# PC104Breakout.net
KiCad netlist of a schematic drawn in Altium Designer
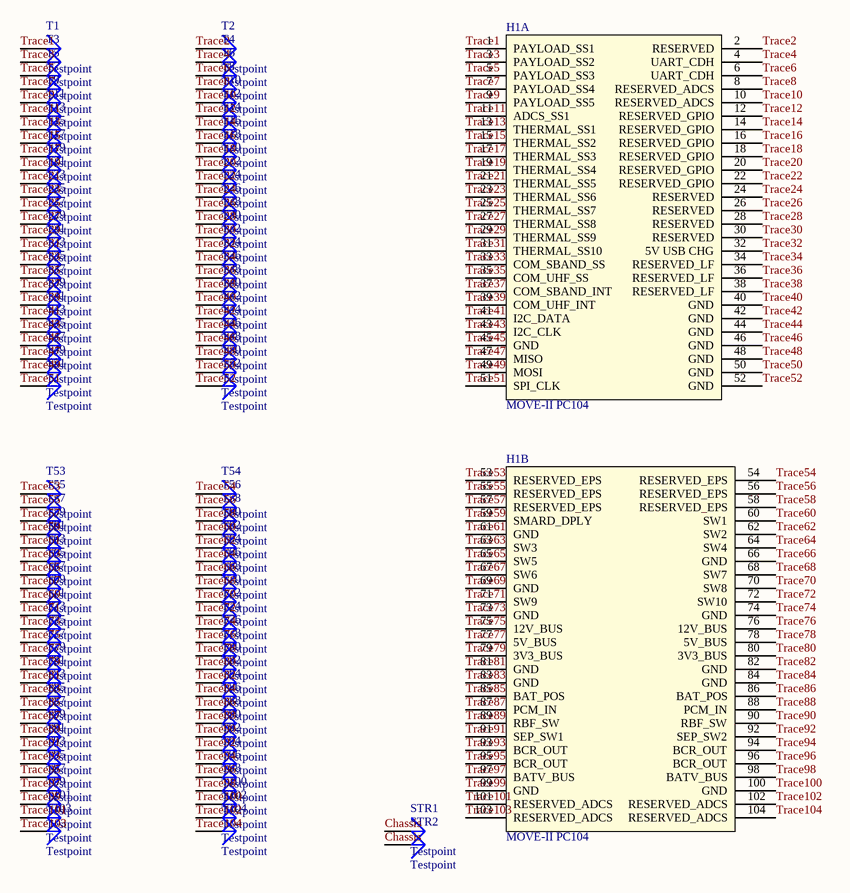
[diagram p0: PC104Breakout.SchDoc]

(export (version "E")
  (design (tool "Eeschema 10.0.6"))
  (components
    (comp (ref "H1")
      (value "MOVE-II PC104")
      (footprint "PC104")
      (libsource (lib "PC104_singleHeader") (part "MOVE-II PC104"))
    )
    (comp (ref "STR1")
      (value "Testpoint")
      (footprint "PIN1")
      (description "Plug")
      (fields (field (name "PUBLISHER") "Altium Limited"))
      (libsource (lib "Miscellaneous Connectors") (part "Plug"))
    )
    (comp (ref "STR2")
      (value "Testpoint")
      (footprint "PIN1")
      (description "Plug")
      (fields (field (name "PUBLISHER") "Altium Limited"))
      (libsource (lib "Miscellaneous Connectors") (part "Plug"))
    )
    (comp (ref "T1")
      (value "Testpoint")
      (footprint "PIN1")
      (description "Plug")
      (fields (field (name "PUBLISHER") "Altium Limited"))
      (libsource (lib "Miscellaneous Connectors") (part "Plug"))
    )
    (comp (ref "T2")
      (value "Testpoint")
      (footprint "PIN1")
      (description "Plug")
      (fields (field (name "PUBLISHER") "Altium Limited"))
      (libsource (lib "Miscellaneous Connectors") (part "Plug"))
    )
    (comp (ref "T3")
      (value "Testpoint")
      (footprint "PIN1")
      (description "Plug")
      (fields (field (name "PUBLISHER") "Altium Limited"))
      (libsource (lib "Miscellaneous Connectors") (part "Plug"))
    )
    (comp (ref "T4")
      (value "Testpoint")
      (footprint "PIN1")
      (description "Plug")
      (fields (field (name "PUBLISHER") "Altium Limited"))
      (libsource (lib "Miscellaneous Connectors") (part "Plug"))
    )
    (comp (ref "T5")
      (value "Testpoint")
      (footprint "PIN1")
      (description "Plug")
      (fields (field (name "PUBLISHER") "Altium Limited"))
      (libsource (lib "Miscellaneous Connectors") (part "Plug"))
    )
    (comp (ref "T6")
      (value "Testpoint")
      (footprint "PIN1")
      (description "Plug")
      (fields (field (name "PUBLISHER") "Altium Limited"))
      (libsource (lib "Miscellaneous Connectors") (part "Plug"))
    )
    (comp (ref "T7")
      (value "Testpoint")
      (footprint "PIN1")
      (description "Plug")
      (fields (field (name "PUBLISHER") "Altium Limited"))
      (libsource (lib "Miscellaneous Connectors") (part "Plug"))
    )
    (comp (ref "T8")
      (value "Testpoint")
      (footprint "PIN1")
      (description "Plug")
      (fields (field (name "PUBLISHER") "Altium Limited"))
      (libsource (lib "Miscellaneous Connectors") (part "Plug"))
    )
    (comp (ref "T9")
      (value "Testpoint")
      (footprint "PIN1")
      (description "Plug")
      (fields (field (name "PUBLISHER") "Altium Limited"))
      (libsource (lib "Miscellaneous Connectors") (part "Plug"))
    )
    (comp (ref "T10")
      (value "Testpoint")
      (footprint "PIN1")
      (description "Plug")
      (fields (field (name "PUBLISHER") "Altium Limited"))
      (libsource (lib "Miscellaneous Connectors") (part "Plug"))
    )
    (comp (ref "T11")
      (value "Testpoint")
      (footprint "PIN1")
      (description "Plug")
      (fields (field (name "PUBLISHER") "Altium Limited"))
      (libsource (lib "Miscellaneous Connectors") (part "Plug"))
    )
    (comp (ref "T12")
      (value "Testpoint")
      (footprint "PIN1")
      (description "Plug")
      (fields (field (name "PUBLISHER") "Altium Limited"))
      (libsource (lib "Miscellaneous Connectors") (part "Plug"))
    )
    (comp (ref "T13")
      (value "Testpoint")
      (footprint "PIN1")
      (description "Plug")
      (fields (field (name "PUBLISHER") "Altium Limited"))
      (libsource (lib "Miscellaneous Connectors") (part "Plug"))
    )
    (comp (ref "T14")
      (value "Testpoint")
      (footprint "PIN1")
      (description "Plug")
      (fields (field (name "PUBLISHER") "Altium Limited"))
      (libsource (lib "Miscellaneous Connectors") (part "Plug"))
    )
    (comp (ref "T15")
      (value "Testpoint")
      (footprint "PIN1")
      (description "Plug")
      (fields (field (name "PUBLISHER") "Altium Limited"))
      (libsource (lib "Miscellaneous Connectors") (part "Plug"))
    )
    (comp (ref "T16")
      (value "Testpoint")
      (footprint "PIN1")
      (description "Plug")
      (fields (field (name "PUBLISHER") "Altium Limited"))
      (libsource (lib "Miscellaneous Connectors") (part "Plug"))
    )
    (comp (ref "T17")
      (value "Testpoint")
      (footprint "PIN1")
      (description "Plug")
      (fields (field (name "PUBLISHER") "Altium Limited"))
      (libsource (lib "Miscellaneous Connectors") (part "Plug"))
    )
    (comp (ref "T18")
      (value "Testpoint")
      (footprint "PIN1")
      (description "Plug")
      (fields (field (name "PUBLISHER") "Altium Limited"))
      (libsource (lib "Miscellaneous Connectors") (part "Plug"))
    )
    (comp (ref "T19")
      (value "Testpoint")
      (footprint "PIN1")
      (description "Plug")
      (fields (field (name "PUBLISHER") "Altium Limited"))
      (libsource (lib "Miscellaneous Connectors") (part "Plug"))
    )
    (comp (ref "T20")
      (value "Testpoint")
      (footprint "PIN1")
      (description "Plug")
      (fields (field (name "PUBLISHER") "Altium Limited"))
      (libsource (lib "Miscellaneous Connectors") (part "Plug"))
    )
    (comp (ref "T21")
      (value "Testpoint")
      (footprint "PIN1")
      (description "Plug")
      (fields (field (name "PUBLISHER") "Altium Limited"))
      (libsource (lib "Miscellaneous Connectors") (part "Plug"))
    )
    (comp (ref "T22")
      (value "Testpoint")
      (footprint "PIN1")
      (description "Plug")
      (fields (field (name "PUBLISHER") "Altium Limited"))
      (libsource (lib "Miscellaneous Connectors") (part "Plug"))
    )
    (comp (ref "T23")
      (value "Testpoint")
      (footprint "PIN1")
      (description "Plug")
      (fields (field (name "PUBLISHER") "Altium Limited"))
      (libsource (lib "Miscellaneous Connectors") (part "Plug"))
    )
    (comp (ref "T24")
      (value "Testpoint")
      (footprint "PIN1")
      (description "Plug")
      (fields (field (name "PUBLISHER") "Altium Limited"))
      (libsource (lib "Miscellaneous Connectors") (part "Plug"))
    )
    (comp (ref "T25")
      (value "Testpoint")
      (footprint "PIN1")
      (description "Plug")
      (fields (field (name "PUBLISHER") "Altium Limited"))
      (libsource (lib "Miscellaneous Connectors") (part "Plug"))
    )
    (comp (ref "T26")
      (value "Testpoint")
      (footprint "PIN1")
      (description "Plug")
      (fields (field (name "PUBLISHER") "Altium Limited"))
      (libsource (lib "Miscellaneous Connectors") (part "Plug"))
    )
    (comp (ref "T27")
      (value "Testpoint")
      (footprint "PIN1")
      (description "Plug")
      (fields (field (name "PUBLISHER") "Altium Limited"))
      (libsource (lib "Miscellaneous Connectors") (part "Plug"))
    )
    (comp (ref "T28")
      (value "Testpoint")
      (footprint "PIN1")
      (description "Plug")
      (fields (field (name "PUBLISHER") "Altium Limited"))
      (libsource (lib "Miscellaneous Connectors") (part "Plug"))
    )
    (comp (ref "T29")
      (value "Testpoint")
      (footprint "PIN1")
      (description "Plug")
      (fields (field (name "PUBLISHER") "Altium Limited"))
      (libsource (lib "Miscellaneous Connectors") (part "Plug"))
    )
    (comp (ref "T30")
      (value "Testpoint")
      (footprint "PIN1")
      (description "Plug")
      (fields (field (name "PUBLISHER") "Altium Limited"))
      (libsource (lib "Miscellaneous Connectors") (part "Plug"))
    )
    (comp (ref "T31")
      (value "Testpoint")
      (footprint "PIN1")
      (description "Plug")
      (fields (field (name "PUBLISHER") "Altium Limited"))
      (libsource (lib "Miscellaneous Connectors") (part "Plug"))
    )
    (comp (ref "T32")
      (value "Testpoint")
      (footprint "PIN1")
      (description "Plug")
      (fields (field (name "PUBLISHER") "Altium Limited"))
      (libsource (lib "Miscellaneous Connectors") (part "Plug"))
    )
    (comp (ref "T33")
      (value "Testpoint")
      (footprint "PIN1")
      (description "Plug")
      (fields (field (name "PUBLISHER") "Altium Limited"))
      (libsource (lib "Miscellaneous Connectors") (part "Plug"))
    )
    (comp (ref "T34")
      (value "Testpoint")
      (footprint "PIN1")
      (description "Plug")
      (fields (field (name "PUBLISHER") "Altium Limited"))
      (libsource (lib "Miscellaneous Connectors") (part "Plug"))
    )
    (comp (ref "T35")
      (value "Testpoint")
      (footprint "PIN1")
      (description "Plug")
      (fields (field (name "PUBLISHER") "Altium Limited"))
      (libsource (lib "Miscellaneous Connectors") (part "Plug"))
    )
    (comp (ref "T36")
      (value "Testpoint")
      (footprint "PIN1")
      (description "Plug")
      (fields (field (name "PUBLISHER") "Altium Limited"))
      (libsource (lib "Miscellaneous Connectors") (part "Plug"))
    )
    (comp (ref "T37")
      (value "Testpoint")
      (footprint "PIN1")
      (description "Plug")
      (fields (field (name "PUBLISHER") "Altium Limited"))
      (libsource (lib "Miscellaneous Connectors") (part "Plug"))
    )
    (comp (ref "T38")
      (value "Testpoint")
      (footprint "PIN1")
      (description "Plug")
      (fields (field (name "PUBLISHER") "Altium Limited"))
      (libsource (lib "Miscellaneous Connectors") (part "Plug"))
    )
    (comp (ref "T39")
      (value "Testpoint")
      (footprint "PIN1")
      (description "Plug")
      (fields (field (name "PUBLISHER") "Altium Limited"))
      (libsource (lib "Miscellaneous Connectors") (part "Plug"))
    )
    (comp (ref "T40")
      (value "Testpoint")
      (footprint "PIN1")
      (description "Plug")
      (fields (field (name "PUBLISHER") "Altium Limited"))
      (libsource (lib "Miscellaneous Connectors") (part "Plug"))
    )
    (comp (ref "T41")
      (value "Testpoint")
      (footprint "PIN1")
      (description "Plug")
      (fields (field (name "PUBLISHER") "Altium Limited"))
      (libsource (lib "Miscellaneous Connectors") (part "Plug"))
    )
    (comp (ref "T42")
      (value "Testpoint")
      (footprint "PIN1")
      (description "Plug")
      (fields (field (name "PUBLISHER") "Altium Limited"))
      (libsource (lib "Miscellaneous Connectors") (part "Plug"))
    )
    (comp (ref "T43")
      (value "Testpoint")
      (footprint "PIN1")
      (description "Plug")
      (fields (field (name "PUBLISHER") "Altium Limited"))
      (libsource (lib "Miscellaneous Connectors") (part "Plug"))
    )
    (comp (ref "T44")
      (value "Testpoint")
      (footprint "PIN1")
      (description "Plug")
      (fields (field (name "PUBLISHER") "Altium Limited"))
      (libsource (lib "Miscellaneous Connectors") (part "Plug"))
    )
    (comp (ref "T45")
      (value "Testpoint")
      (footprint "PIN1")
      (description "Plug")
      (fields (field (name "PUBLISHER") "Altium Limited"))
      (libsource (lib "Miscellaneous Connectors") (part "Plug"))
    )
    (comp (ref "T46")
      (value "Testpoint")
      (footprint "PIN1")
      (description "Plug")
      (fields (field (name "PUBLISHER") "Altium Limited"))
      (libsource (lib "Miscellaneous Connectors") (part "Plug"))
    )
    (comp (ref "T47")
      (value "Testpoint")
      (footprint "PIN1")
      (description "Plug")
      (fields (field (name "PUBLISHER") "Altium Limited"))
      (libsource (lib "Miscellaneous Connectors") (part "Plug"))
    )
    (comp (ref "T48")
      (value "Testpoint")
      (footprint "PIN1")
      (description "Plug")
      (fields (field (name "PUBLISHER") "Altium Limited"))
      (libsource (lib "Miscellaneous Connectors") (part "Plug"))
    )
    (comp (ref "T49")
      (value "Testpoint")
      (footprint "PIN1")
      (description "Plug")
      (fields (field (name "PUBLISHER") "Altium Limited"))
      (libsource (lib "Miscellaneous Connectors") (part "Plug"))
    )
    (comp (ref "T50")
      (value "Testpoint")
      (footprint "PIN1")
      (description "Plug")
      (fields (field (name "PUBLISHER") "Altium Limited"))
      (libsource (lib "Miscellaneous Connectors") (part "Plug"))
    )
    (comp (ref "T51")
      (value "Testpoint")
      (footprint "PIN1")
      (description "Plug")
      (fields (field (name "PUBLISHER") "Altium Limited"))
      (libsource (lib "Miscellaneous Connectors") (part "Plug"))
    )
    (comp (ref "T52")
      (value "Testpoint")
      (footprint "PIN1")
      (description "Plug")
      (fields (field (name "PUBLISHER") "Altium Limited"))
      (libsource (lib "Miscellaneous Connectors") (part "Plug"))
    )
    (comp (ref "T53")
      (value "Testpoint")
      (footprint "PIN1")
      (description "Plug")
      (fields (field (name "PUBLISHER") "Altium Limited"))
      (libsource (lib "Miscellaneous Connectors") (part "Plug"))
    )
    (comp (ref "T54")
      (value "Testpoint")
      (footprint "PIN1")
      (description "Plug")
      (fields (field (name "PUBLISHER") "Altium Limited"))
      (libsource (lib "Miscellaneous Connectors") (part "Plug"))
    )
    (comp (ref "T55")
      (value "Testpoint")
      (footprint "PIN1")
      (description "Plug")
      (fields (field (name "PUBLISHER") "Altium Limited"))
      (libsource (lib "Miscellaneous Connectors") (part "Plug"))
    )
    (comp (ref "T56")
      (value "Testpoint")
      (footprint "PIN1")
      (description "Plug")
      (fields (field (name "PUBLISHER") "Altium Limited"))
      (libsource (lib "Miscellaneous Connectors") (part "Plug"))
    )
    (comp (ref "T57")
      (value "Testpoint")
      (footprint "PIN1")
      (description "Plug")
      (fields (field (name "PUBLISHER") "Altium Limited"))
      (libsource (lib "Miscellaneous Connectors") (part "Plug"))
    )
    (comp (ref "T58")
      (value "Testpoint")
      (footprint "PIN1")
      (description "Plug")
      (fields (field (name "PUBLISHER") "Altium Limited"))
      (libsource (lib "Miscellaneous Connectors") (part "Plug"))
    )
    (comp (ref "T59")
      (value "Testpoint")
      (footprint "PIN1")
      (description "Plug")
      (fields (field (name "PUBLISHER") "Altium Limited"))
      (libsource (lib "Miscellaneous Connectors") (part "Plug"))
    )
    (comp (ref "T60")
      (value "Testpoint")
      (footprint "PIN1")
      (description "Plug")
      (fields (field (name "PUBLISHER") "Altium Limited"))
      (libsource (lib "Miscellaneous Connectors") (part "Plug"))
    )
    (comp (ref "T61")
      (value "Testpoint")
      (footprint "PIN1")
      (description "Plug")
      (fields (field (name "PUBLISHER") "Altium Limited"))
      (libsource (lib "Miscellaneous Connectors") (part "Plug"))
    )
    (comp (ref "T62")
      (value "Testpoint")
      (footprint "PIN1")
      (description "Plug")
      (fields (field (name "PUBLISHER") "Altium Limited"))
      (libsource (lib "Miscellaneous Connectors") (part "Plug"))
    )
    (comp (ref "T63")
      (value "Testpoint")
      (footprint "PIN1")
      (description "Plug")
      (fields (field (name "PUBLISHER") "Altium Limited"))
      (libsource (lib "Miscellaneous Connectors") (part "Plug"))
    )
    (comp (ref "T64")
      (value "Testpoint")
      (footprint "PIN1")
      (description "Plug")
      (fields (field (name "PUBLISHER") "Altium Limited"))
      (libsource (lib "Miscellaneous Connectors") (part "Plug"))
    )
    (comp (ref "T65")
      (value "Testpoint")
      (footprint "PIN1")
      (description "Plug")
      (fields (field (name "PUBLISHER") "Altium Limited"))
      (libsource (lib "Miscellaneous Connectors") (part "Plug"))
    )
    (comp (ref "T66")
      (value "Testpoint")
      (footprint "PIN1")
      (description "Plug")
      (fields (field (name "PUBLISHER") "Altium Limited"))
      (libsource (lib "Miscellaneous Connectors") (part "Plug"))
    )
    (comp (ref "T67")
      (value "Testpoint")
      (footprint "PIN1")
      (description "Plug")
      (fields (field (name "PUBLISHER") "Altium Limited"))
      (libsource (lib "Miscellaneous Connectors") (part "Plug"))
    )
    (comp (ref "T68")
      (value "Testpoint")
      (footprint "PIN1")
      (description "Plug")
      (fields (field (name "PUBLISHER") "Altium Limited"))
      (libsource (lib "Miscellaneous Connectors") (part "Plug"))
    )
    (comp (ref "T69")
      (value "Testpoint")
      (footprint "PIN1")
      (description "Plug")
      (fields (field (name "PUBLISHER") "Altium Limited"))
      (libsource (lib "Miscellaneous Connectors") (part "Plug"))
    )
    (comp (ref "T70")
      (value "Testpoint")
      (footprint "PIN1")
      (description "Plug")
      (fields (field (name "PUBLISHER") "Altium Limited"))
      (libsource (lib "Miscellaneous Connectors") (part "Plug"))
    )
    (comp (ref "T71")
      (value "Testpoint")
      (footprint "PIN1")
      (description "Plug")
      (fields (field (name "PUBLISHER") "Altium Limited"))
      (libsource (lib "Miscellaneous Connectors") (part "Plug"))
    )
    (comp (ref "T72")
      (value "Testpoint")
      (footprint "PIN1")
      (description "Plug")
      (fields (field (name "PUBLISHER") "Altium Limited"))
      (libsource (lib "Miscellaneous Connectors") (part "Plug"))
    )
    (comp (ref "T73")
      (value "Testpoint")
      (footprint "PIN1")
      (description "Plug")
      (fields (field (name "PUBLISHER") "Altium Limited"))
      (libsource (lib "Miscellaneous Connectors") (part "Plug"))
    )
    (comp (ref "T74")
      (value "Testpoint")
      (footprint "PIN1")
      (description "Plug")
      (fields (field (name "PUBLISHER") "Altium Limited"))
      (libsource (lib "Miscellaneous Connectors") (part "Plug"))
    )
    (comp (ref "T75")
      (value "Testpoint")
      (footprint "PIN1")
      (description "Plug")
      (fields (field (name "PUBLISHER") "Altium Limited"))
      (libsource (lib "Miscellaneous Connectors") (part "Plug"))
    )
    (comp (ref "T76")
      (value "Testpoint")
      (footprint "PIN1")
      (description "Plug")
      (fields (field (name "PUBLISHER") "Altium Limited"))
      (libsource (lib "Miscellaneous Connectors") (part "Plug"))
    )
    (comp (ref "T77")
      (value "Testpoint")
      (footprint "PIN1")
      (description "Plug")
      (fields (field (name "PUBLISHER") "Altium Limited"))
      (libsource (lib "Miscellaneous Connectors") (part "Plug"))
    )
    (comp (ref "T78")
      (value "Testpoint")
      (footprint "PIN1")
      (description "Plug")
      (fields (field (name "PUBLISHER") "Altium Limited"))
      (libsource (lib "Miscellaneous Connectors") (part "Plug"))
    )
    (comp (ref "T79")
      (value "Testpoint")
      (footprint "PIN1")
      (description "Plug")
      (fields (field (name "PUBLISHER") "Altium Limited"))
      (libsource (lib "Miscellaneous Connectors") (part "Plug"))
    )
    (comp (ref "T80")
      (value "Testpoint")
      (footprint "PIN1")
      (description "Plug")
      (fields (field (name "PUBLISHER") "Altium Limited"))
      (libsource (lib "Miscellaneous Connectors") (part "Plug"))
    )
    (comp (ref "T81")
      (value "Testpoint")
      (footprint "PIN1")
      (description "Plug")
      (fields (field (name "PUBLISHER") "Altium Limited"))
      (libsource (lib "Miscellaneous Connectors") (part "Plug"))
    )
    (comp (ref "T82")
      (value "Testpoint")
      (footprint "PIN1")
      (description "Plug")
      (fields (field (name "PUBLISHER") "Altium Limited"))
      (libsource (lib "Miscellaneous Connectors") (part "Plug"))
    )
    (comp (ref "T83")
      (value "Testpoint")
      (footprint "PIN1")
      (description "Plug")
      (fields (field (name "PUBLISHER") "Altium Limited"))
      (libsource (lib "Miscellaneous Connectors") (part "Plug"))
    )
    (comp (ref "T84")
      (value "Testpoint")
      (footprint "PIN1")
      (description "Plug")
      (fields (field (name "PUBLISHER") "Altium Limited"))
      (libsource (lib "Miscellaneous Connectors") (part "Plug"))
    )
    (comp (ref "T85")
      (value "Testpoint")
      (footprint "PIN1")
      (description "Plug")
      (fields (field (name "PUBLISHER") "Altium Limited"))
      (libsource (lib "Miscellaneous Connectors") (part "Plug"))
    )
    (comp (ref "T86")
      (value "Testpoint")
      (footprint "PIN1")
      (description "Plug")
      (fields (field (name "PUBLISHER") "Altium Limited"))
      (libsource (lib "Miscellaneous Connectors") (part "Plug"))
    )
    (comp (ref "T87")
      (value "Testpoint")
      (footprint "PIN1")
      (description "Plug")
      (fields (field (name "PUBLISHER") "Altium Limited"))
      (libsource (lib "Miscellaneous Connectors") (part "Plug"))
    )
    (comp (ref "T88")
      (value "Testpoint")
      (footprint "PIN1")
      (description "Plug")
      (fields (field (name "PUBLISHER") "Altium Limited"))
      (libsource (lib "Miscellaneous Connectors") (part "Plug"))
    )
    (comp (ref "T89")
      (value "Testpoint")
      (footprint "PIN1")
      (description "Plug")
      (fields (field (name "PUBLISHER") "Altium Limited"))
      (libsource (lib "Miscellaneous Connectors") (part "Plug"))
    )
    (comp (ref "T90")
      (value "Testpoint")
      (footprint "PIN1")
      (description "Plug")
      (fields (field (name "PUBLISHER") "Altium Limited"))
      (libsource (lib "Miscellaneous Connectors") (part "Plug"))
    )
    (comp (ref "T91")
      (value "Testpoint")
      (footprint "PIN1")
      (description "Plug")
      (fields (field (name "PUBLISHER") "Altium Limited"))
      (libsource (lib "Miscellaneous Connectors") (part "Plug"))
    )
    (comp (ref "T92")
      (value "Testpoint")
      (footprint "PIN1")
      (description "Plug")
      (fields (field (name "PUBLISHER") "Altium Limited"))
      (libsource (lib "Miscellaneous Connectors") (part "Plug"))
    )
    (comp (ref "T93")
      (value "Testpoint")
      (footprint "PIN1")
      (description "Plug")
      (fields (field (name "PUBLISHER") "Altium Limited"))
      (libsource (lib "Miscellaneous Connectors") (part "Plug"))
    )
    (comp (ref "T94")
      (value "Testpoint")
      (footprint "PIN1")
      (description "Plug")
      (fields (field (name "PUBLISHER") "Altium Limited"))
      (libsource (lib "Miscellaneous Connectors") (part "Plug"))
    )
    (comp (ref "T95")
      (value "Testpoint")
      (footprint "PIN1")
      (description "Plug")
      (fields (field (name "PUBLISHER") "Altium Limited"))
      (libsource (lib "Miscellaneous Connectors") (part "Plug"))
    )
    (comp (ref "T96")
      (value "Testpoint")
      (footprint "PIN1")
      (description "Plug")
      (fields (field (name "PUBLISHER") "Altium Limited"))
      (libsource (lib "Miscellaneous Connectors") (part "Plug"))
    )
    (comp (ref "T97")
      (value "Testpoint")
      (footprint "PIN1")
      (description "Plug")
      (fields (field (name "PUBLISHER") "Altium Limited"))
      (libsource (lib "Miscellaneous Connectors") (part "Plug"))
    )
    (comp (ref "T98")
      (value "Testpoint")
      (footprint "PIN1")
      (description "Plug")
      (fields (field (name "PUBLISHER") "Altium Limited"))
      (libsource (lib "Miscellaneous Connectors") (part "Plug"))
    )
    (comp (ref "T99")
      (value "Testpoint")
      (footprint "PIN1")
      (description "Plug")
      (fields (field (name "PUBLISHER") "Altium Limited"))
      (libsource (lib "Miscellaneous Connectors") (part "Plug"))
    )
    (comp (ref "T100")
      (value "Testpoint")
      (footprint "PIN1")
      (description "Plug")
      (fields (field (name "PUBLISHER") "Altium Limited"))
      (libsource (lib "Miscellaneous Connectors") (part "Plug"))
    )
    (comp (ref "T101")
      (value "Testpoint")
      (footprint "PIN1")
      (description "Plug")
      (fields (field (name "PUBLISHER") "Altium Limited"))
      (libsource (lib "Miscellaneous Connectors") (part "Plug"))
    )
    (comp (ref "T102")
      (value "Testpoint")
      (footprint "PIN1")
      (description "Plug")
      (fields (field (name "PUBLISHER") "Altium Limited"))
      (libsource (lib "Miscellaneous Connectors") (part "Plug"))
    )
    (comp (ref "T103")
      (value "Testpoint")
      (footprint "PIN1")
      (description "Plug")
      (fields (field (name "PUBLISHER") "Altium Limited"))
      (libsource (lib "Miscellaneous Connectors") (part "Plug"))
    )
    (comp (ref "T104")
      (value "Testpoint")
      (footprint "PIN1")
      (description "Plug")
      (fields (field (name "PUBLISHER") "Altium Limited"))
      (libsource (lib "Miscellaneous Connectors") (part "Plug"))
    )
  )
  (nets
    (net (code "1") (name "/Chassis") (class "Default")
      (node (ref "STR1") (pin "1") (pinfunction "1_1") (pintype "passive"))
      (node (ref "STR2") (pin "1") (pinfunction "1_1") (pintype "passive"))
    )
    (net (code "2") (name "/Trace1") (class "Default")
      (node (ref "H1") (pin "1") (pinfunction "PAYLOAD_SS1_1") (pintype "passive"))
      (node (ref "T1") (pin "1") (pinfunction "1_1") (pintype "passive"))
    )
    (net (code "3") (name "/Trace2") (class "Default")
      (node (ref "H1") (pin "2") (pinfunction "RESERVED_2") (pintype "passive"))
      (node (ref "T2") (pin "1") (pinfunction "1_1") (pintype "passive"))
    )
    (net (code "4") (name "/Trace3") (class "Default")
      (node (ref "H1") (pin "3") (pinfunction "PAYLOAD_SS2_3") (pintype "passive"))
      (node (ref "T3") (pin "1") (pinfunction "1_1") (pintype "passive"))
    )
    (net (code "5") (name "/Trace4") (class "Default")
      (node (ref "H1") (pin "4") (pinfunction "UART_CDH_4") (pintype "passive"))
      (node (ref "T4") (pin "1") (pinfunction "1_1") (pintype "passive"))
    )
    (net (code "6") (name "/Trace5") (class "Default")
      (node (ref "H1") (pin "5") (pinfunction "PAYLOAD_SS3_5") (pintype "passive"))
      (node (ref "T5") (pin "1") (pinfunction "1_1") (pintype "passive"))
    )
    (net (code "7") (name "/Trace6") (class "Default")
      (node (ref "H1") (pin "6") (pinfunction "UART_CDH_6") (pintype "passive"))
      (node (ref "T6") (pin "1") (pinfunction "1_1") (pintype "passive"))
    )
    (net (code "8") (name "/Trace7") (class "Default")
      (node (ref "H1") (pin "7") (pinfunction "PAYLOAD_SS4_7") (pintype "passive"))
      (node (ref "T7") (pin "1") (pinfunction "1_1") (pintype "passive"))
    )
    (net (code "9") (name "/Trace8") (class "Default")
      (node (ref "H1") (pin "8") (pinfunction "RESERVED_ADCS_8") (pintype "passive"))
      (node (ref "T8") (pin "1") (pinfunction "1_1") (pintype "passive"))
    )
    (net (code "10") (name "/Trace9") (class "Default")
      (node (ref "H1") (pin "9") (pinfunction "PAYLOAD_SS5_9") (pintype "passive"))
      (node (ref "T9") (pin "1") (pinfunction "1_1") (pintype "passive"))
    )
    (net (code "11") (name "/Trace10") (class "Default")
      (node (ref "H1") (pin "10") (pinfunction "RESERVED_ADCS_10") (pintype "passive"))
      (node (ref "T10") (pin "1") (pinfunction "1_1") (pintype "passive"))
    )
    (net (code "12") (name "/Trace11") (class "Default")
      (node (ref "H1") (pin "11") (pinfunction "ADCS_SS1_11") (pintype "passive"))
      (node (ref "T11") (pin "1") (pinfunction "1_1") (pintype "passive"))
    )
    (net (code "13") (name "/Trace12") (class "Default")
      (node (ref "H1") (pin "12") (pinfunction "RESERVED_GPIO_12") (pintype "passive"))
      (node (ref "T12") (pin "1") (pinfunction "1_1") (pintype "passive"))
    )
    (net (code "14") (name "/Trace13") (class "Default")
      (node (ref "H1") (pin "13") (pinfunction "THERMAL_SS1_13") (pintype "passive"))
      (node (ref "T13") (pin "1") (pinfunction "1_1") (pintype "passive"))
    )
    (net (code "15") (name "/Trace14") (class "Default")
      (node (ref "H1") (pin "14") (pinfunction "RESERVED_GPIO_14") (pintype "passive"))
      (node (ref "T14") (pin "1") (pinfunction "1_1") (pintype "passive"))
    )
    (net (code "16") (name "/Trace15") (class "Default")
      (node (ref "H1") (pin "15") (pinfunction "THERMAL_SS2_15") (pintype "passive"))
      (node (ref "T15") (pin "1") (pinfunction "1_1") (pintype "passive"))
    )
    (net (code "17") (name "/Trace16") (class "Default")
      (node (ref "H1") (pin "16") (pinfunction "RESERVED_GPIO_16") (pintype "passive"))
      (node (ref "T16") (pin "1") (pinfunction "1_1") (pintype "passive"))
    )
    (net (code "18") (name "/Trace17") (class "Default")
      (node (ref "H1") (pin "17") (pinfunction "THERMAL_SS3_17") (pintype "passive"))
      (node (ref "T17") (pin "1") (pinfunction "1_1") (pintype "passive"))
    )
    (net (code "19") (name "/Trace18") (class "Default")
      (node (ref "H1") (pin "18") (pinfunction "RESERVED_GPIO_18") (pintype "passive"))
      (node (ref "T18") (pin "1") (pinfunction "1_1") (pintype "passive"))
    )
    (net (code "20") (name "/Trace19") (class "Default")
      (node (ref "H1") (pin "19") (pinfunction "THERMAL_SS4_19") (pintype "passive"))
      (node (ref "T19") (pin "1") (pinfunction "1_1") (pintype "passive"))
    )
    (net (code "21") (name "/Trace20") (class "Default")
      (node (ref "H1") (pin "20") (pinfunction "RESERVED_GPIO_20") (pintype "passive"))
      (node (ref "T20") (pin "1") (pinfunction "1_1") (pintype "passive"))
    )
    (net (code "22") (name "/Trace21") (class "Default")
      (node (ref "H1") (pin "21") (pinfunction "THERMAL_SS5_21") (pintype "passive"))
      (node (ref "T21") (pin "1") (pinfunction "1_1") (pintype "passive"))
    )
    (net (code "23") (name "/Trace22") (class "Default")
      (node (ref "H1") (pin "22") (pinfunction "RESERVED_GPIO_22") (pintype "passive"))
      (node (ref "T22") (pin "1") (pinfunction "1_1") (pintype "passive"))
    )
    (net (code "24") (name "/Trace23") (class "Default")
      (node (ref "H1") (pin "23") (pinfunction "THERMAL_SS6_23") (pintype "passive"))
      (node (ref "T23") (pin "1") (pinfunction "1_1") (pintype "passive"))
    )
    (net (code "25") (name "/Trace24") (class "Default")
      (node (ref "H1") (pin "24") (pinfunction "RESERVED_24") (pintype "passive"))
      (node (ref "T24") (pin "1") (pinfunction "1_1") (pintype "passive"))
    )
    (net (code "26") (name "/Trace25") (class "Default")
      (node (ref "H1") (pin "25") (pinfunction "THERMAL_SS7_25") (pintype "passive"))
      (node (ref "T25") (pin "1") (pinfunction "1_1") (pintype "passive"))
    )
    (net (code "27") (name "/Trace26") (class "Default")
      (node (ref "H1") (pin "26") (pinfunction "RESERVED_26") (pintype "passive"))
      (node (ref "T26") (pin "1") (pinfunction "1_1") (pintype "passive"))
    )
    (net (code "28") (name "/Trace27") (class "Default")
      (node (ref "H1") (pin "27") (pinfunction "THERMAL_SS8_27") (pintype "passive"))
      (node (ref "T27") (pin "1") (pinfunction "1_1") (pintype "passive"))
    )
    (net (code "29") (name "/Trace28") (class "Default")
      (node (ref "H1") (pin "28") (pinfunction "RESERVED_28") (pintype "passive"))
      (node (ref "T28") (pin "1") (pinfunction "1_1") (pintype "passive"))
    )
    (net (code "30") (name "/Trace29") (class "Default")
      (node (ref "H1") (pin "29") (pinfunction "THERMAL_SS9_29") (pintype "passive"))
      (node (ref "T29") (pin "1") (pinfunction "1_1") (pintype "passive"))
    )
    (net (code "31") (name "/Trace30") (class "Default")
      (node (ref "H1") (pin "30") (pinfunction "RESERVED_30") (pintype "passive"))
      (node (ref "T30") (pin "1") (pinfunction "1_1") (pintype "passive"))
    )
    (net (code "32") (name "/Trace31") (class "Default")
      (node (ref "H1") (pin "31") (pinfunction "THERMAL_SS10_31") (pintype "passive"))
      (node (ref "T31") (pin "1") (pinfunction "1_1") (pintype "passive"))
    )
    (net (code "33") (name "/Trace32") (class "Default")
      (node (ref "H1") (pin "32") (pinfunction "5V_USB_CHG_32") (pintype "passive"))
      (node (ref "T32") (pin "1") (pinfunction "1_1") (pintype "passive"))
    )
    (net (code "34") (name "/Trace33") (class "Default")
      (node (ref "H1") (pin "33") (pinfunction "COM_SBAND_SS_33") (pintype "passive"))
      (node (ref "T33") (pin "1") (pinfunction "1_1") (pintype "passive"))
    )
    (net (code "35") (name "/Trace34") (class "Default")
      (node (ref "H1") (pin "34") (pinfunction "RESERVED_LF_34") (pintype "passive"))
      (node (ref "T34") (pin "1") (pinfunction "1_1") (pintype "passive"))
    )
    (net (code "36") (name "/Trace35") (class "Default")
      (node (ref "H1") (pin "35") (pinfunction "COM_UHF_SS_35") (pintype "passive"))
      (node (ref "T35") (pin "1") (pinfunction "1_1") (pintype "passive"))
    )
    (net (code "37") (name "/Trace36") (class "Default")
      (node (ref "H1") (pin "36") (pinfunction "RESERVED_LF_36") (pintype "passive"))
      (node (ref "T36") (pin "1") (pinfunction "1_1") (pintype "passive"))
    )
    (net (code "38") (name "/Trace37") (class "Default")
      (node (ref "H1") (pin "37") (pinfunction "COM_SBAND_INT_37") (pintype "passive"))
      (node (ref "T37") (pin "1") (pinfunction "1_1") (pintype "passive"))
    )
    (net (code "39") (name "/Trace38") (class "Default")
      (node (ref "H1") (pin "38") (pinfunction "RESERVED_LF_38") (pintype "passive"))
      (node (ref "T38") (pin "1") (pinfunction "1_1") (pintype "passive"))
    )
    (net (code "40") (name "/Trace39") (class "Default")
      (node (ref "H1") (pin "39") (pinfunction "COM_UHF_INT_39") (pintype "passive"))
      (node (ref "T39") (pin "1") (pinfunction "1_1") (pintype "passive"))
    )
    (net (code "41") (name "/Trace40") (class "Default")
      (node (ref "H1") (pin "40") (pinfunction "GND_40") (pintype "passive"))
      (node (ref "T40") (pin "1") (pinfunction "1_1") (pintype "passive"))
    )
    (net (code "42") (name "/Trace41") (class "Default")
      (node (ref "H1") (pin "41") (pinfunction "I2C_DATA_41") (pintype "passive"))
      (node (ref "T41") (pin "1") (pinfunction "1_1") (pintype "passive"))
    )
    (net (code "43") (name "/Trace42") (class "Default")
      (node (ref "H1") (pin "42") (pinfunction "GND_42") (pintype "passive"))
      (node (ref "T42") (pin "1") (pinfunction "1_1") (pintype "passive"))
    )
    (net (code "44") (name "/Trace43") (class "Default")
      (node (ref "H1") (pin "43") (pinfunction "I2C_CLK_43") (pintype "passive"))
      (node (ref "T43") (pin "1") (pinfunction "1_1") (pintype "passive"))
    )
    (net (code "45") (name "/Trace44") (class "Default")
      (node (ref "H1") (pin "44") (pinfunction "GND_44") (pintype "passive"))
      (node (ref "T44") (pin "1") (pinfunction "1_1") (pintype "passive"))
    )
    (net (code "46") (name "/Trace45") (class "Default")
      (node (ref "H1") (pin "45") (pinfunction "GND_45") (pintype "passive"))
      (node (ref "T45") (pin "1") (pinfunction "1_1") (pintype "passive"))
    )
    (net (code "47") (name "/Trace46") (class "Default")
      (node (ref "H1") (pin "46") (pinfunction "GND_46") (pintype "passive"))
      (node (ref "T46") (pin "1") (pinfunction "1_1") (pintype "passive"))
    )
    (net (code "48") (name "/Trace47") (class "Default")
      (node (ref "H1") (pin "47") (pinfunction "MISO_47") (pintype "passive"))
      (node (ref "T47") (pin "1") (pinfunction "1_1") (pintype "passive"))
    )
    (net (code "49") (name "/Trace48") (class "Default")
      (node (ref "H1") (pin "48") (pinfunction "GND_48") (pintype "passive"))
      (node (ref "T48") (pin "1") (pinfunction "1_1") (pintype "passive"))
    )
    (net (code "50") (name "/Trace49") (class "Default")
      (node (ref "H1") (pin "49") (pinfunction "MOSI_49") (pintype "passive"))
      (node (ref "T49") (pin "1") (pinfunction "1_1") (pintype "passive"))
    )
    (net (code "51") (name "/Trace50") (class "Default")
      (node (ref "H1") (pin "50") (pinfunction "GND_50") (pintype "passive"))
      (node (ref "T50") (pin "1") (pinfunction "1_1") (pintype "passive"))
    )
    (net (code "52") (name "/Trace51") (class "Default")
      (node (ref "H1") (pin "51") (pinfunction "SPI_CLK_51") (pintype "passive"))
      (node (ref "T51") (pin "1") (pinfunction "1_1") (pintype "passive"))
    )
    (net (code "53") (name "/Trace52") (class "Default")
      (node (ref "H1") (pin "52") (pinfunction "GND_52") (pintype "passive"))
      (node (ref "T52") (pin "1") (pinfunction "1_1") (pintype "passive"))
    )
    (net (code "54") (name "/Trace53") (class "Default")
      (node (ref "H1") (pin "53") (pinfunction "RESERVED_EPS_53") (pintype "passive"))
      (node (ref "T53") (pin "1") (pinfunction "1_1") (pintype "passive"))
    )
    (net (code "55") (name "/Trace54") (class "Default")
      (node (ref "H1") (pin "54") (pinfunction "RESERVED_EPS_54") (pintype "passive"))
      (node (ref "T54") (pin "1") (pinfunction "1_1") (pintype "passive"))
    )
    (net (code "56") (name "/Trace55") (class "Default")
      (node (ref "H1") (pin "55") (pinfunction "RESERVED_EPS_55") (pintype "passive"))
      (node (ref "T55") (pin "1") (pinfunction "1_1") (pintype "passive"))
    )
    (net (code "57") (name "/Trace56") (class "Default")
      (node (ref "H1") (pin "56") (pinfunction "RESERVED_EPS_56") (pintype "passive"))
      (node (ref "T56") (pin "1") (pinfunction "1_1") (pintype "passive"))
    )
    (net (code "58") (name "/Trace57") (class "Default")
      (node (ref "H1") (pin "57") (pinfunction "RESERVED_EPS_57") (pintype "passive"))
      (node (ref "T57") (pin "1") (pinfunction "1_1") (pintype "passive"))
    )
    (net (code "59") (name "/Trace58") (class "Default")
      (node (ref "H1") (pin "58") (pinfunction "RESERVED_EPS_58") (pintype "passive"))
      (node (ref "T58") (pin "1") (pinfunction "1_1") (pintype "passive"))
    )
    (net (code "60") (name "/Trace59") (class "Default")
      (node (ref "H1") (pin "59") (pinfunction "SMARD_DPLY_59") (pintype "passive"))
      (node (ref "T59") (pin "1") (pinfunction "1_1") (pintype "passive"))
    )
    (net (code "61") (name "/Trace60") (class "Default")
      (node (ref "H1") (pin "60") (pinfunction "SW1_60") (pintype "passive"))
      (node (ref "T60") (pin "1") (pinfunction "1_1") (pintype "passive"))
    )
    (net (code "62") (name "/Trace61") (class "Default")
      (node (ref "H1") (pin "61") (pinfunction "GND_61") (pintype "passive"))
      (node (ref "T61") (pin "1") (pinfunction "1_1") (pintype "passive"))
    )
    (net (code "63") (name "/Trace62") (class "Default")
      (node (ref "H1") (pin "62") (pinfunction "SW2_62") (pintype "passive"))
      (node (ref "T62") (pin "1") (pinfunction "1_1") (pintype "passive"))
    )
    (net (code "64") (name "/Trace63") (class "Default")
      (node (ref "H1") (pin "63") (pinfunction "SW3_63") (pintype "passive"))
      (node (ref "T63") (pin "1") (pinfunction "1_1") (pintype "passive"))
    )
    (net (code "65") (name "/Trace64") (class "Default")
      (node (ref "H1") (pin "64") (pinfunction "SW4_64") (pintype "passive"))
      (node (ref "T64") (pin "1") (pinfunction "1_1") (pintype "passive"))
    )
    (net (code "66") (name "/Trace65") (class "Default")
      (node (ref "H1") (pin "65") (pinfunction "SW5_65") (pintype "passive"))
      (node (ref "T65") (pin "1") (pinfunction "1_1") (pintype "passive"))
    )
    (net (code "67") (name "/Trace66") (class "Default")
      (node (ref "H1") (pin "66") (pinfunction "GND_66") (pintype "passive"))
      (node (ref "T66") (pin "1") (pinfunction "1_1") (pintype "passive"))
    )
    (net (code "68") (name "/Trace67") (class "Default")
      (node (ref "H1") (pin "67") (pinfunction "SW6_67") (pintype "passive"))
      (node (ref "T67") (pin "1") (pinfunction "1_1") (pintype "passive"))
    )
    (net (code "69") (name "/Trace68") (class "Default")
      (node (ref "H1") (pin "68") (pinfunction "SW7_68") (pintype "passive"))
      (node (ref "T68") (pin "1") (pinfunction "1_1") (pintype "passive"))
    )
    (net (code "70") (name "/Trace69") (class "Default")
      (node (ref "H1") (pin "69") (pinfunction "GND_69") (pintype "passive"))
      (node (ref "T69") (pin "1") (pinfunction "1_1") (pintype "passive"))
    )
    (net (code "71") (name "/Trace70") (class "Default")
      (node (ref "H1") (pin "70") (pinfunction "SW8_70") (pintype "passive"))
      (node (ref "T70") (pin "1") (pinfunction "1_1") (pintype "passive"))
    )
    (net (code "72") (name "/Trace71") (class "Default")
      (node (ref "H1") (pin "71") (pinfunction "SW9_71") (pintype "passive"))
      (node (ref "T71") (pin "1") (pinfunction "1_1") (pintype "passive"))
    )
    (net (code "73") (name "/Trace72") (class "Default")
      (node (ref "H1") (pin "72") (pinfunction "SW10_72") (pintype "passive"))
      (node (ref "T72") (pin "1") (pinfunction "1_1") (pintype "passive"))
    )
    (net (code "74") (name "/Trace73") (class "Default")
      (node (ref "H1") (pin "73") (pinfunction "GND_73") (pintype "passive"))
      (node (ref "T73") (pin "1") (pinfunction "1_1") (pintype "passive"))
    )
    (net (code "75") (name "/Trace74") (class "Default")
      (node (ref "H1") (pin "74") (pinfunction "GND_74") (pintype "passive"))
      (node (ref "T74") (pin "1") (pinfunction "1_1") (pintype "passive"))
    )
    (net (code "76") (name "/Trace75") (class "Default")
      (node (ref "H1") (pin "75") (pinfunction "12V_BUS_75") (pintype "passive"))
      (node (ref "T75") (pin "1") (pinfunction "1_1") (pintype "passive"))
    )
    (net (code "77") (name "/Trace76") (class "Default")
      (node (ref "H1") (pin "76") (pinfunction "12V_BUS_76") (pintype "passive"))
      (node (ref "T76") (pin "1") (pinfunction "1_1") (pintype "passive"))
    )
    (net (code "78") (name "/Trace77") (class "Default")
      (node (ref "H1") (pin "77") (pinfunction "5V_BUS_77") (pintype "passive"))
      (node (ref "T77") (pin "1") (pinfunction "1_1") (pintype "passive"))
    )
    (net (code "79") (name "/Trace78") (class "Default")
      (node (ref "H1") (pin "78") (pinfunction "5V_BUS_78") (pintype "passive"))
      (node (ref "T78") (pin "1") (pinfunction "1_1") (pintype "passive"))
    )
    (net (code "80") (name "/Trace79") (class "Default")
      (node (ref "H1") (pin "79") (pinfunction "3V3_BUS_79") (pintype "passive"))
      (node (ref "T79") (pin "1") (pinfunction "1_1") (pintype "passive"))
    )
    (net (code "81") (name "/Trace80") (class "Default")
      (node (ref "H1") (pin "80") (pinfunction "3V3_BUS_80") (pintype "passive"))
      (node (ref "T80") (pin "1") (pinfunction "1_1") (pintype "passive"))
    )
    (net (code "82") (name "/Trace81") (class "Default")
      (node (ref "H1") (pin "81") (pinfunction "GND_81") (pintype "passive"))
      (node (ref "T81") (pin "1") (pinfunction "1_1") (pintype "passive"))
    )
    (net (code "83") (name "/Trace82") (class "Default")
      (node (ref "H1") (pin "82") (pinfunction "GND_82") (pintype "passive"))
      (node (ref "T82") (pin "1") (pinfunction "1_1") (pintype "passive"))
    )
    (net (code "84") (name "/Trace83") (class "Default")
      (node (ref "H1") (pin "83") (pinfunction "GND_83") (pintype "passive"))
      (node (ref "T83") (pin "1") (pinfunction "1_1") (pintype "passive"))
    )
    (net (code "85") (name "/Trace84") (class "Default")
      (node (ref "H1") (pin "84") (pinfunction "GND_84") (pintype "passive"))
      (node (ref "T84") (pin "1") (pinfunction "1_1") (pintype "passive"))
    )
    (net (code "86") (name "/Trace85") (class "Default")
      (node (ref "H1") (pin "85") (pinfunction "BAT_POS_85") (pintype "passive"))
      (node (ref "T85") (pin "1") (pinfunction "1_1") (pintype "passive"))
    )
    (net (code "87") (name "/Trace86") (class "Default")
      (node (ref "H1") (pin "86") (pinfunction "BAT_POS_86") (pintype "passive"))
      (node (ref "T86") (pin "1") (pinfunction "1_1") (pintype "passive"))
    )
    (net (code "88") (name "/Trace87") (class "Default")
      (node (ref "H1") (pin "87") (pinfunction "PCM_IN_87") (pintype "passive"))
      (node (ref "T87") (pin "1") (pinfunction "1_1") (pintype "passive"))
    )
    (net (code "89") (name "/Trace88") (class "Default")
      (node (ref "H1") (pin "88") (pinfunction "PCM_IN_88") (pintype "passive"))
      (node (ref "T88") (pin "1") (pinfunction "1_1") (pintype "passive"))
    )
    (net (code "90") (name "/Trace89") (class "Default")
      (node (ref "H1") (pin "89") (pinfunction "RBF_SW_89") (pintype "passive"))
      (node (ref "T89") (pin "1") (pinfunction "1_1") (pintype "passive"))
    )
    (net (code "91") (name "/Trace90") (class "Default")
      (node (ref "H1") (pin "90") (pinfunction "RBF_SW_90") (pintype "passive"))
      (node (ref "T90") (pin "1") (pinfunction "1_1") (pintype "passive"))
    )
    (net (code "92") (name "/Trace91") (class "Default")
      (node (ref "H1") (pin "91") (pinfunction "SEP_SW1_91") (pintype "passive"))
      (node (ref "T91") (pin "1") (pinfunction "1_1") (pintype "passive"))
    )
    (net (code "93") (name "/Trace92") (class "Default")
      (node (ref "H1") (pin "92") (pinfunction "SEP_SW2_92") (pintype "passive"))
      (node (ref "T92") (pin "1") (pinfunction "1_1") (pintype "passive"))
    )
    (net (code "94") (name "/Trace93") (class "Default")
      (node (ref "H1") (pin "93") (pinfunction "BCR_OUT_93") (pintype "passive"))
      (node (ref "T93") (pin "1") (pinfunction "1_1") (pintype "passive"))
    )
    (net (code "95") (name "/Trace94") (class "Default")
      (node (ref "H1") (pin "94") (pinfunction "BCR_OUT_94") (pintype "passive"))
      (node (ref "T94") (pin "1") (pinfunction "1_1") (pintype "passive"))
    )
    (net (code "96") (name "/Trace95") (class "Default")
      (node (ref "H1") (pin "95") (pinfunction "BCR_OUT_95") (pintype "passive"))
      (node (ref "T95") (pin "1") (pinfunction "1_1") (pintype "passive"))
    )
    (net (code "97") (name "/Trace96") (class "Default")
      (node (ref "H1") (pin "96") (pinfunction "BCR_OUT_96") (pintype "passive"))
      (node (ref "T96") (pin "1") (pinfunction "1_1") (pintype "passive"))
    )
    (net (code "98") (name "/Trace97") (class "Default")
      (node (ref "H1") (pin "97") (pinfunction "BATV_BUS_97") (pintype "passive"))
      (node (ref "T97") (pin "1") (pinfunction "1_1") (pintype "passive"))
    )
    (net (code "99") (name "/Trace98") (class "Default")
      (node (ref "H1") (pin "98") (pinfunction "BATV_BUS_98") (pintype "passive"))
      (node (ref "T98") (pin "1") (pinfunction "1_1") (pintype "passive"))
    )
    (net (code "100") (name "/Trace99") (class "Default")
      (node (ref "H1") (pin "99") (pinfunction "GND_99") (pintype "passive"))
      (node (ref "T99") (pin "1") (pinfunction "1_1") (pintype "passive"))
    )
    (net (code "101") (name "/Trace100") (class "Default")
      (node (ref "H1") (pin "100") (pinfunction "GND_100") (pintype "passive"))
      (node (ref "T100") (pin "1") (pinfunction "1_1") (pintype "passive"))
    )
    (net (code "102") (name "/Trace101") (class "Default")
      (node (ref "H1") (pin "101") (pinfunction "RESERVED_ADCS_101") (pintype "passive"))
      (node (ref "T101") (pin "1") (pinfunction "1_1") (pintype "passive"))
    )
    (net (code "103") (name "/Trace102") (class "Default")
      (node (ref "H1") (pin "102") (pinfunction "RESERVED_ADCS_102") (pintype "passive"))
      (node (ref "T102") (pin "1") (pinfunction "1_1") (pintype "passive"))
    )
    (net (code "104") (name "/Trace103") (class "Default")
      (node (ref "H1") (pin "103") (pinfunction "RESERVED_ADCS_103") (pintype "passive"))
      (node (ref "T103") (pin "1") (pinfunction "1_1") (pintype "passive"))
    )
    (net (code "105") (name "/Trace104") (class "Default")
      (node (ref "H1") (pin "104") (pinfunction "RESERVED_ADCS_104") (pintype "passive"))
      (node (ref "T104") (pin "1") (pinfunction "1_1") (pintype "passive"))
    )
  )
)
